# Morpheus_MCU.net
KiCad netlist of a schematic drawn in Altium Designer
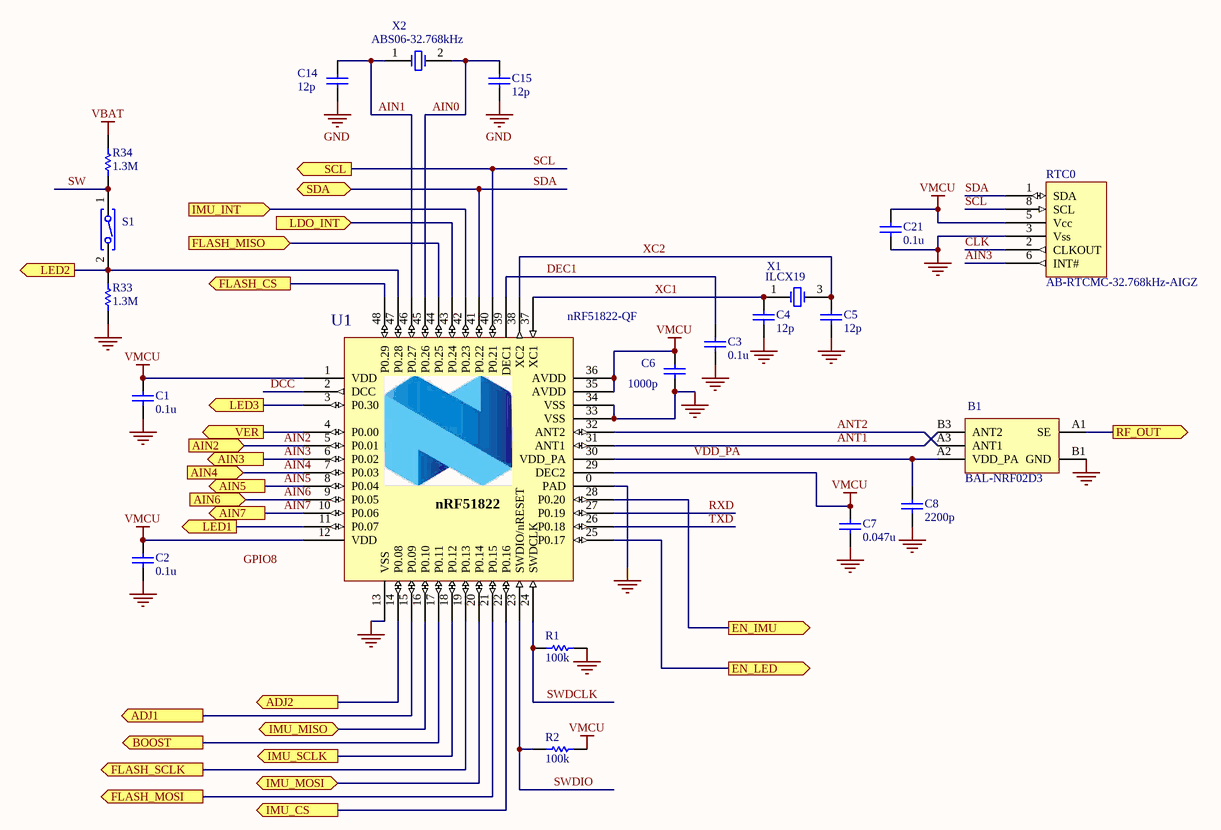
[diagram p0: Morpheus_MCU.SchDoc]

(export (version "E")
  (design (tool "Eeschema 10.0.6"))
  (components
    (comp (ref "B1")
      (value "BAL-NRF02D3")
      (footprint "BAL-ST-WLCSP")
      (description "50 ohm balun transformer for 2.45GHz ISM")
      (fields (field (name "MANUFACTURER") "ST") (field (name "PUBLISHER") "Nordic Semiconductor"))
      (libsource (lib "nrf51822_ceaa") (part "BAL-ST-5pin_DC-Flip"))
    )
    (comp (ref "C1")
      (value "0.1u")
      (footprint "CAP0402")
      (description "Chip capacitor")
      (fields (field (name "TOLERANCE") "10%") (field (name "VOLTAGE") "50V"))
      (libsource (lib "Hello") (part "C_0.1u_10_50_X7R_0402"))
    )
    (comp (ref "C2")
      (value "0.1u")
      (footprint "CAP0402")
      (description "Chip capacitor")
      (fields (field (name "TOLERANCE") "10%") (field (name "VOLTAGE") "50V"))
      (libsource (lib "Hello") (part "C_0.1u_10_50_X7R_0402"))
    )
    (comp (ref "C3")
      (value "0.1u")
      (footprint "CAP0402")
      (description "Chip capacitor")
      (fields (field (name "TOLERANCE") "10%") (field (name "VOLTAGE") "50V"))
      (libsource (lib "Hello") (part "C_0.1u_10_50_X7R_0402"))
    )
    (comp (ref "C4")
      (value "12p")
      (footprint "CAP0402")
      (description "Chip capacitor")
      (fields (field (name "TOLERANCE") "5%") (field (name "VOLTAGE") "50V"))
      (libsource (lib "Hello") (part "C_27p_5_50_C0G_0402"))
    )
    (comp (ref "C5")
      (value "12p")
      (footprint "CAP0402")
      (description "Chip capacitor")
      (fields (field (name "TOLERANCE") "5%") (field (name "VOLTAGE") "50V"))
      (libsource (lib "Hello") (part "C_27p_5_50_C0G_0402"))
    )
    (comp (ref "C6")
      (value "1000p")
      (footprint "CAP0402")
      (description "Chip capacitor")
      (fields (field (name "TOLERANCE") "10%") (field (name "VOLTAGE") "50V"))
      (libsource (lib "Hello") (part "C_1000p_10_50_X7R_0402"))
    )
    (comp (ref "C7")
      (value "0.047u")
      (footprint "CAP0402")
      (description "Chip capacitor")
      (fields (field (name "TOLERANCE") "10%") (field (name "VOLTAGE") "16V"))
      (libsource (lib "Hello") (part "C_0.047u_10_16_X7R_0402"))
    )
    (comp (ref "C8")
      (value "2200p")
      (footprint "CAP0402")
      (description "Chip capacitor")
      (fields (field (name "TOLERANCE") "5 %") (field (name "VOLTAGE") "16V"))
      (libsource (lib "Hello") (part "C_2200p_5_16_STD_0402"))
    )
    (comp (ref "C14")
      (value "12p")
      (footprint "CAP0402")
      (description "Chip capacitor")
      (fields (field (name "TOLERANCE") "5%") (field (name "VOLTAGE") "50V"))
      (libsource (lib "Hello") (part "C_27p_5_50_C0G_0402"))
    )
    (comp (ref "C15")
      (value "12p")
      (footprint "CAP0402")
      (description "Chip capacitor")
      (fields (field (name "TOLERANCE") "5%") (field (name "VOLTAGE") "50V"))
      (libsource (lib "Hello") (part "C_27p_5_50_C0G_0402"))
    )
    (comp (ref "C21")
      (value "0.1u")
      (footprint "CAP0402")
      (description "Chip capacitor")
      (fields (field (name "TOLERANCE") "10%") (field (name "VOLTAGE") "50V"))
      (libsource (lib "Hello") (part "C_0.1u_10_50_X7R_0402"))
    )
    (comp (ref "R1")
      (value "100k")
      (footprint "RES0402")
      (description "Chip Resistor")
      (fields (field (name "TOLERANCE") "1 %") (field (name "POWER") "0.1 W"))
      (libsource (lib "Hello") (part "R_100k_1_0.1_0402"))
    )
    (comp (ref "R2")
      (value "100k")
      (footprint "RES0402")
      (description "Chip Resistor")
      (fields (field (name "TOLERANCE") "1 %") (field (name "POWER") "0.1 W"))
      (libsource (lib "Hello") (part "R_100k_1_0.1_0402"))
    )
    (comp (ref "R33")
      (value "1.3M")
      (footprint "RES0402")
      (description "Chip Resistor")
      (fields (field (name "TOLERANCE") "5 %") (field (name "POWER") "0.1 W"))
      (libsource (lib "Hello") (part "R_1.3M_5_0.1_0402_1"))
    )
    (comp (ref "R34")
      (value "1.3M")
      (footprint "RES0402")
      (description "Chip Resistor")
      (fields (field (name "TOLERANCE") "5 %") (field (name "POWER") "0.1 W"))
      (libsource (lib "Hello") (part "R_1.3M_5_0.1_0402_1"))
    )
    (comp (ref "RTC0")
      (value "AB-RTCMC-32.768kHz-AIGZ")
      (footprint "8-CLCC")
      (description "Abracon I2C RTC w/ integrated XO")
      (libsource (lib "Hello") (part "AB-RTCMC-32.768kHz-AIGZ"))
    )
    (comp (ref "S1")
      (value "REED_SPST_NO")
      (footprint "REED-10x1.8")
      (description "SWITCH REED SPST NO")
      (libsource (lib "Hello") (part "SW_REED_SPST_NO"))
    )
    (comp (ref "U1")
      (value "nRF51822-QF")
      (footprint "VQFN40P600X600X100-48")
      (description "Multi-protocol Bluetooth Low Energy and 2.4GHz proprietary system-on-chip")
      (fields
        (field (name "MANUFACTURER") "Nordic Semiconductor")
        (field (name "PUBLISHER") "Nordic Semiconductor")
      )
      (libsource (lib "Mopd") (part "nRF51822_QF"))
    )
    (comp (ref "X1")
      (value "ILCX19")
      (footprint "ILCX19")
      (description "ILSI ILCX19 Crystal Oscillator")
      (libsource (lib "Hello") (part "ILCX19"))
    )
    (comp (ref "X2")
      (value "ABS06-32.768kHz")
      (footprint "ABS06")
      (description "Abracon ABS06 32.768kHz XO 2.0x1.2x0.6mm")
      (libsource (lib "Hello") (part "ABS06"))
    )
  )
  (nets
    (net (code "1") (name "/ADJ1") (class "Default")
      (node (ref "U1") (pin "15") (pinfunction "P0.09_15") (pintype "bidirectional"))
    )
    (net (code "2") (name "/ADJ2") (class "Default")
      (node (ref "U1") (pin "14") (pinfunction "P0.08_14") (pintype "bidirectional"))
    )
    (net (code "3") (name "/AIN0") (class "Default")
      (node (ref "C15") (pin "2") (pinfunction "2_2") (pintype "passive"))
      (node (ref "U1") (pin "45") (pinfunction "P0.26_45") (pintype "bidirectional"))
      (node (ref "X2") (pin "2") (pinfunction "2_2") (pintype "passive"))
    )
    (net (code "4") (name "/AIN1") (class "Default")
      (node (ref "C14") (pin "2") (pinfunction "2_2") (pintype "passive"))
      (node (ref "U1") (pin "46") (pinfunction "P0.27_46") (pintype "bidirectional"))
      (node (ref "X2") (pin "1") (pinfunction "1_1") (pintype "passive"))
    )
    (net (code "5") (name "/AIN2") (class "Default")
      (node (ref "U1") (pin "5") (pinfunction "P0.01_5") (pintype "bidirectional"))
    )
    (net (code "6") (name "/AIN3") (class "Default")
      (node (ref "RTC0") (pin "6") (pinfunction "INT#_6") (pintype "output"))
      (node (ref "U1") (pin "6") (pinfunction "P0.02_6") (pintype "bidirectional"))
    )
    (net (code "7") (name "/AIN4") (class "Default")
      (node (ref "U1") (pin "7") (pinfunction "P0.03_7") (pintype "bidirectional"))
    )
    (net (code "8") (name "/AIN5") (class "Default")
      (node (ref "U1") (pin "8") (pinfunction "P0.04_8") (pintype "bidirectional"))
    )
    (net (code "9") (name "/AIN6") (class "Default")
      (node (ref "U1") (pin "9") (pinfunction "P0.05_9") (pintype "bidirectional"))
    )
    (net (code "10") (name "/AIN7") (class "Default")
      (node (ref "U1") (pin "10") (pinfunction "P0.06_10") (pintype "bidirectional"))
    )
    (net (code "11") (name "/ANT1") (class "Default")
      (node (ref "B1") (pin "B3") (pinfunction "ANT2_B3") (pintype "passive"))
      (node (ref "U1") (pin "31") (pinfunction "ANT1_31") (pintype "bidirectional"))
    )
    (net (code "12") (name "/ANT2") (class "Default")
      (node (ref "B1") (pin "A3") (pinfunction "ANT1_A3") (pintype "passive"))
      (node (ref "U1") (pin "32") (pinfunction "ANT2_32") (pintype "bidirectional"))
    )
    (net (code "13") (name "/BOOST") (class "Default")
      (node (ref "U1") (pin "17") (pinfunction "P0.11_17") (pintype "bidirectional"))
    )
    (net (code "14") (name "/CLK") (class "Default")
      (node (ref "RTC0") (pin "2") (pinfunction "CLKOUT_2") (pintype "output"))
    )
    (net (code "15") (name "/DCC") (class "Default")
      (node (ref "U1") (pin "2") (pinfunction "DCC_2") (pintype "output"))
    )
    (net (code "16") (name "/DEC1") (class "Default")
      (node (ref "C3") (pin "2") (pinfunction "2_2") (pintype "passive"))
      (node (ref "U1") (pin "39") (pinfunction "DEC1_39") (pintype "power_in"))
    )
    (net (code "17") (name "/EN_IMU") (class "Default")
      (node (ref "U1") (pin "28") (pinfunction "P0.20_28") (pintype "bidirectional"))
    )
    (net (code "18") (name "/EN_LED") (class "Default")
      (node (ref "U1") (pin "25") (pinfunction "P0.17_25") (pintype "bidirectional"))
    )
    (net (code "19") (name "/FLASH_CS") (class "Default")
      (node (ref "U1") (pin "48") (pinfunction "P0.29_48") (pintype "bidirectional"))
    )
    (net (code "20") (name "/FLASH_MISO") (class "Default")
      (node (ref "U1") (pin "44") (pinfunction "P0.25_44") (pintype "bidirectional"))
    )
    (net (code "21") (name "/FLASH_MOSI") (class "Default")
      (node (ref "U1") (pin "21") (pinfunction "P0.15_21") (pintype "bidirectional"))
    )
    (net (code "22") (name "/FLASH_SCLK") (class "Default")
      (node (ref "U1") (pin "19") (pinfunction "P0.13_19") (pintype "bidirectional"))
    )
    (net (code "24") (name "/IMU_CS") (class "Default")
      (node (ref "U1") (pin "22") (pinfunction "P0.16_22") (pintype "bidirectional"))
    )
    (net (code "25") (name "/IMU_INT") (class "Default")
      (node (ref "U1") (pin "42") (pinfunction "P0.23_42") (pintype "bidirectional"))
    )
    (net (code "26") (name "/IMU_MISO") (class "Default")
      (node (ref "U1") (pin "16") (pinfunction "P0.10_16") (pintype "bidirectional"))
    )
    (net (code "27") (name "/IMU_MOSI") (class "Default")
      (node (ref "U1") (pin "20") (pinfunction "P0.14_20") (pintype "bidirectional"))
    )
    (net (code "28") (name "/IMU_SCLK") (class "Default")
      (node (ref "U1") (pin "18") (pinfunction "P0.12_18") (pintype "bidirectional"))
    )
    (net (code "29") (name "/LDO_INT") (class "Default")
      (node (ref "U1") (pin "43") (pinfunction "P0.24_43") (pintype "bidirectional"))
    )
    (net (code "30") (name "/LED1") (class "Default")
      (node (ref "U1") (pin "11") (pinfunction "P0.07_11") (pintype "bidirectional"))
    )
    (net (code "31") (name "/LED2") (class "Default")
      (node (ref "R33") (pin "2") (pinfunction "2_2") (pintype "passive"))
      (node (ref "S1") (pin "2") (pinfunction "2_2") (pintype "passive"))
      (node (ref "U1") (pin "47") (pinfunction "P0.28_47") (pintype "bidirectional"))
    )
    (net (code "32") (name "/LED3") (class "Default")
      (node (ref "U1") (pin "3") (pinfunction "P0.30_3") (pintype "bidirectional"))
    )
    (net (code "33") (name "/RF_OUT") (class "Default")
      (node (ref "B1") (pin "A1") (pinfunction "SE_A1") (pintype "passive"))
    )
    (net (code "34") (name "/RXD") (class "Default")
      (node (ref "U1") (pin "27") (pinfunction "P0.19_27") (pintype "bidirectional"))
    )
    (net (code "35") (name "/SCL") (class "Default")
      (node (ref "RTC0") (pin "8") (pinfunction "SCL_8") (pintype "input"))
      (node (ref "U1") (pin "40") (pinfunction "P0.21_40") (pintype "bidirectional"))
    )
    (net (code "36") (name "/SDA") (class "Default")
      (node (ref "RTC0") (pin "1") (pinfunction "SDA_1") (pintype "bidirectional"))
      (node (ref "U1") (pin "41") (pinfunction "P0.22_41") (pintype "bidirectional"))
    )
    (net (code "37") (name "/SW") (class "Default")
      (node (ref "R34") (pin "1") (pinfunction "1_1") (pintype "passive"))
      (node (ref "S1") (pin "1") (pinfunction "1_1") (pintype "passive"))
    )
    (net (code "38") (name "/SWDCLK") (class "Default")
      (node (ref "R1") (pin "1") (pinfunction "1_1") (pintype "passive"))
      (node (ref "U1") (pin "24") (pinfunction "SWDCLK_24") (pintype "input"))
    )
    (net (code "39") (name "/SWDIO") (class "Default")
      (node (ref "R2") (pin "1") (pinfunction "1_1") (pintype "passive"))
      (node (ref "U1") (pin "23") (pinfunction "SWDIO/nRESET_23") (pintype "input"))
    )
    (net (code "40") (name "/TXD") (class "Default")
      (node (ref "U1") (pin "26") (pinfunction "P0.18_26") (pintype "bidirectional"))
    )
    (net (code "41") (name "/VDD_PA") (class "Default")
      (node (ref "B1") (pin "A2") (pinfunction "VDD_PA_A2") (pintype "passive"))
      (node (ref "C8") (pin "2") (pinfunction "2_2") (pintype "passive"))
      (node (ref "U1") (pin "30") (pinfunction "VDD_PA_30") (pintype "power_in"))
    )
    (net (code "42") (name "/VER") (class "Default")
      (node (ref "U1") (pin "4") (pinfunction "P0.00_4") (pintype "bidirectional"))
    )
    (net (code "43") (name "/XC1") (class "Default")
      (node (ref "C4") (pin "2") (pinfunction "2_2") (pintype "passive"))
      (node (ref "U1") (pin "37") (pinfunction "XC1_37") (pintype "input"))
      (node (ref "X1") (pin "1") (pinfunction "XTAL1_1") (pintype "passive"))
    )
    (net (code "44") (name "/XC2") (class "Default")
      (node (ref "C5") (pin "2") (pinfunction "2_2") (pintype "passive"))
      (node (ref "U1") (pin "38") (pinfunction "XC2_38") (pintype "output"))
      (node (ref "X1") (pin "3") (pinfunction "XTAL2_3") (pintype "passive"))
    )
    (net (code "45") (name "GND") (class "Default")
      (node (ref "B1") (pin "B1") (pinfunction "GND_B1") (pintype "passive"))
      (node (ref "C1") (pin "1") (pinfunction "1_1") (pintype "passive"))
      (node (ref "C14") (pin "1") (pinfunction "1_1") (pintype "passive"))
      (node (ref "C15") (pin "1") (pinfunction "1_1") (pintype "passive"))
      (node (ref "C2") (pin "1") (pinfunction "1_1") (pintype "passive"))
      (node (ref "C21") (pin "1") (pinfunction "1_1") (pintype "passive"))
      (node (ref "C3") (pin "1") (pinfunction "1_1") (pintype "passive"))
      (node (ref "C4") (pin "1") (pinfunction "1_1") (pintype "passive"))
      (node (ref "C5") (pin "1") (pinfunction "1_1") (pintype "passive"))
      (node (ref "C6") (pin "1") (pinfunction "1_1") (pintype "passive"))
      (node (ref "C7") (pin "1") (pinfunction "1_1") (pintype "passive"))
      (node (ref "C8") (pin "1") (pinfunction "1_1") (pintype "passive"))
      (node (ref "R1") (pin "2") (pinfunction "2_2") (pintype "passive"))
      (node (ref "R33") (pin "1") (pinfunction "1_1") (pintype "passive"))
      (node (ref "RTC0") (pin "3") (pinfunction "Vss_3") (pintype "power_in"))
      (node (ref "U1") (pin "0") (pinfunction "PAD_0") (pintype "power_in"))
      (node (ref "U1") (pin "13") (pinfunction "VSS_13") (pintype "power_in"))
      (node (ref "U1") (pin "33") (pinfunction "VSS_33") (pintype "power_in"))
      (node (ref "U1") (pin "34") (pinfunction "VSS_34") (pintype "power_in"))
    )
    (net (code "46") (name "VBAT") (class "Default")
      (node (ref "R34") (pin "2") (pinfunction "2_2") (pintype "passive"))
    )
    (net (code "47") (name "VMCU") (class "Default")
      (node (ref "C1") (pin "2") (pinfunction "2_2") (pintype "passive"))
      (node (ref "C2") (pin "2") (pinfunction "2_2") (pintype "passive"))
      (node (ref "C21") (pin "2") (pinfunction "2_2") (pintype "passive"))
      (node (ref "C6") (pin "2") (pinfunction "2_2") (pintype "passive"))
      (node (ref "C7") (pin "2") (pinfunction "2_2") (pintype "passive"))
      (node (ref "R2") (pin "2") (pinfunction "2_2") (pintype "passive"))
      (node (ref "RTC0") (pin "5") (pinfunction "Vcc_5") (pintype "power_in"))
      (node (ref "U1") (pin "1") (pinfunction "VDD_1") (pintype "power_in"))
      (node (ref "U1") (pin "12") (pinfunction "VDD_12") (pintype "power_in"))
      (node (ref "U1") (pin "29") (pinfunction "DEC2_29") (pintype "power_in"))
      (node (ref "U1") (pin "35") (pinfunction "AVDD_35") (pintype "power_in"))
      (node (ref "U1") (pin "36") (pinfunction "AVDD_36") (pintype "power_in"))
    )
    (net (code "48") (name "unconnected-(RTC0-NC-Pad4)") (class "Default")
      (node (ref "RTC0") (pin "4") (pinfunction "NC_4") (pintype "passive"))
    )
    (net (code "49") (name "unconnected-(RTC0-NC-Pad7)") (class "Default")
      (node (ref "RTC0") (pin "7") (pinfunction "NC_7") (pintype "passive"))
    )
  )
)
